# Microcontroller.net
KiCad netlist of a schematic drawn in Altium Designer
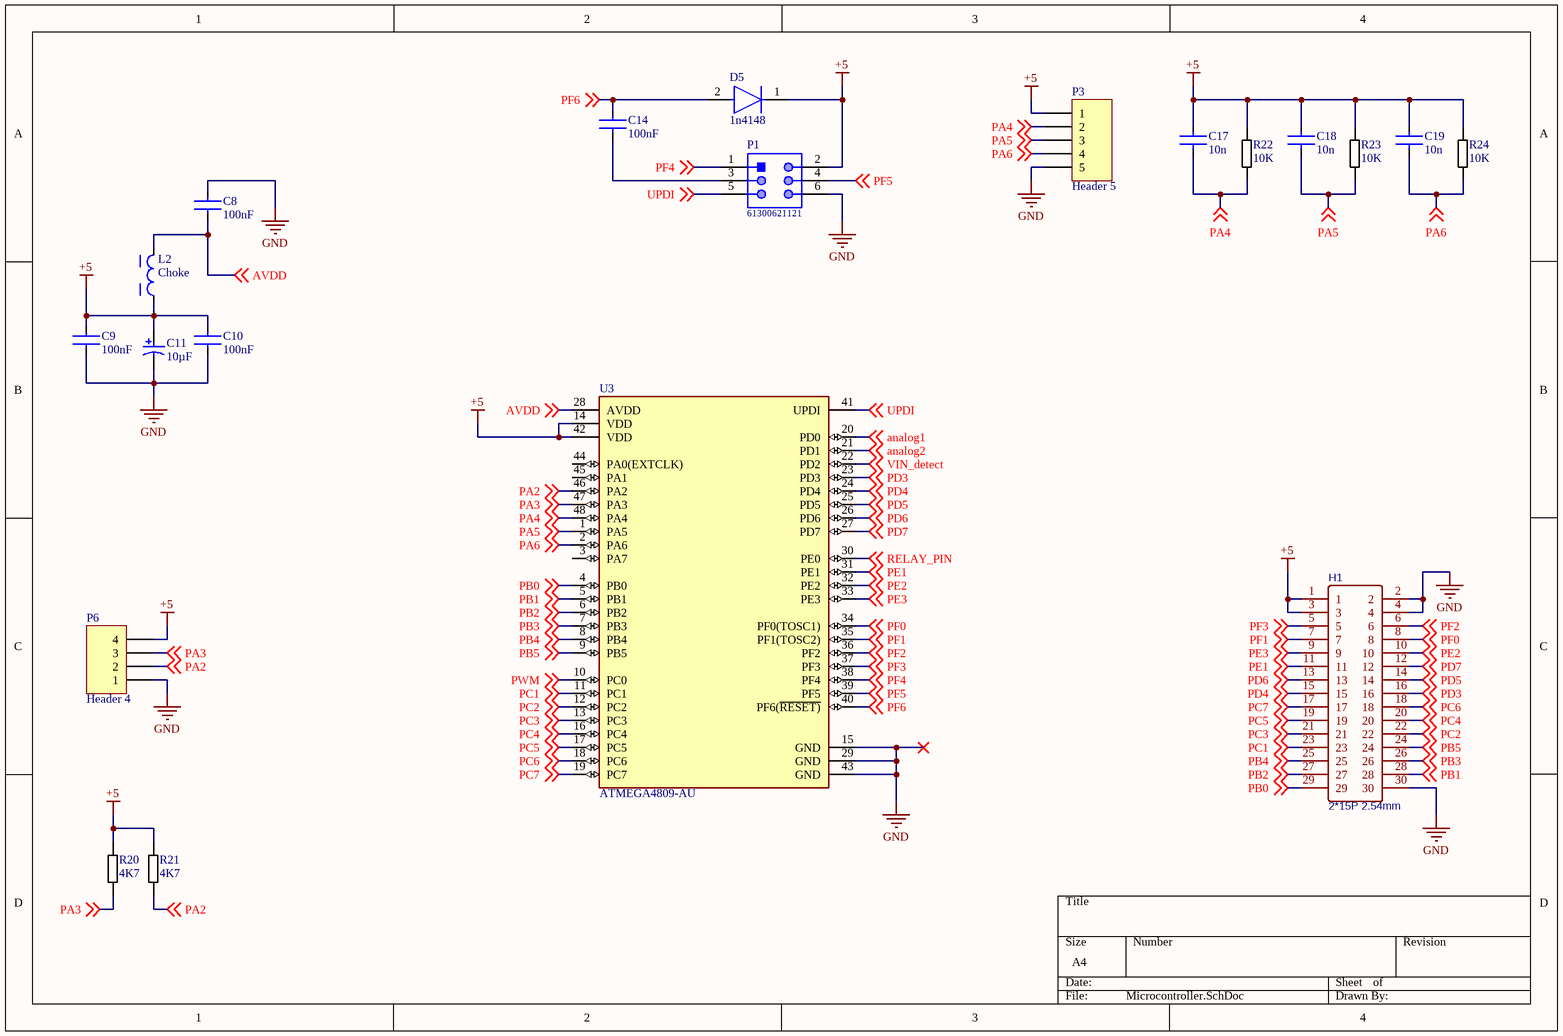
[diagram p0: Microcontroller.SchDoc]

(export (version "E")
  (design (tool "Eeschema 10.0.6"))
  (components
    (comp (ref "C8")
      (value "100nF")
      (footprint "RESC2013X50X30ML20T20")
      (fields (field (name "VOLTAGE") "6.3V") (field (name "TOLERANCE") "20%"))
      (libsource (lib "Soldeerstation") (part "Capacitor"))
    )
    (comp (ref "C9")
      (value "100nF")
      (footprint "RESC2013X50X30ML20T20")
      (fields (field (name "VOLTAGE") "6.3V") (field (name "TOLERANCE") "20%"))
      (libsource (lib "Soldeerstation") (part "Capacitor"))
    )
    (comp (ref "C10")
      (value "100nF")
      (footprint "RESC2013X50X30ML20T20")
      (fields (field (name "VOLTAGE") "6.3V") (field (name "TOLERANCE") "20%"))
      (libsource (lib "Soldeerstation") (part "Capacitor"))
    )
    (comp (ref "C11")
      (value "10µF")
      (footprint "CAP-SMD_BD4.0-L4.3-W4.3-FD-LS5.3")
      (fields (field (name "MANUFACTURER") "Panasonic"))
      (libsource (lib "Soldeerstation") (part "Electrolytic capacitor"))
    )
    (comp (ref "C14")
      (value "100nF")
      (footprint "RESC2013X50X30ML20T20")
      (fields (field (name "VOLTAGE") "6.3V") (field (name "TOLERANCE") "20%"))
      (libsource (lib "Soldeerstation") (part "Capacitor"))
    )
    (comp (ref "C17")
      (value "10n")
      (footprint "RESC2013X50X30ML20T20")
      (fields (field (name "VOLTAGE") "6.3V") (field (name "TOLERANCE") "20%"))
      (libsource (lib "Soldeerstation") (part "Capacitor"))
    )
    (comp (ref "C18")
      (value "10n")
      (footprint "RESC2013X50X30ML20T20")
      (fields (field (name "VOLTAGE") "6.3V") (field (name "TOLERANCE") "20%"))
      (libsource (lib "Soldeerstation") (part "Capacitor"))
    )
    (comp (ref "C19")
      (value "10n")
      (footprint "RESC2013X50X30ML20T20")
      (fields (field (name "VOLTAGE") "6.3V") (field (name "TOLERANCE") "20%"))
      (libsource (lib "Soldeerstation") (part "Capacitor"))
    )
    (comp (ref "D5")
      (value "1n4148")
      (footprint "SOD-123FL")
      (fields
        (field (name "OCTOPART") "https://octopart.com/1n4007-e3%2F54-vishay-39548207")
        (field (name "MANUFACTURER") "Vishay")
        (field (name "MANUFACTURER PART NUMBER") "1N4007-E3/54")
      )
      (libsource (lib "Soldeerstation") (part "Diode"))
    )
    (comp (ref "H1")
      (value "2*15P 2.54mm")
      (footprint "HDR-TH_30P-P2.54-V-M-R2-C15-S2.54")
      (fields
        (field (name "BOM_SUPPLIER PART") "C169817")
        (field (name "BOM_MANUFACTURER PART") "B-2100S30P-B110")
        (field (name "CONTRIBUTOR") "LCSC")
      )
      (libsource (lib "Soldeerstation") (part "2*15P 2.54mm"))
    )
    (comp (ref "L2")
      (value "Choke")
      (footprint "RESC2013X50X30ML20T20")
      (fields (field (name "TOLERANCE") "20%"))
      (libsource (lib "Soldeerstation") (part "Choke"))
    )
    (comp (ref "P1")
      (value "61300621121")
      (footprint "61300621121")
      (description "THT Vertical Pin Header WR-PHD, Pitch 2.54 mm, Dual Row, 6 pins")
      (fields (field (name "MANUFACTURER") "Wurth Elektronik") (field (name "PUBLISHER") "WurthElektronik"))
      (libsource (lib "Altium Content Vault") (part "WE-CN-2P-M-R6"))
    )
    (comp (ref "P3")
      (value "Header 5")
      (footprint "HDR1X5")
      (description "Header, 5-Pin")
      (fields (field (name "PUBLISHER") "Altium Limited"))
      (libsource (lib "Miscellaneous Connectors") (part "Header 5"))
    )
    (comp (ref "P6")
      (value "Header 4")
      (footprint "HDR1X4")
      (description "Header, 4-Pin")
      (fields (field (name "PUBLISHER") "Altium Limited"))
      (libsource (lib "Miscellaneous Connectors") (part "Header 4"))
    )
    (comp (ref "R20")
      (value "4K7")
      (footprint "RESC2013X50X30ML20T20")
      (fields (field (name "MANUFACTURER") "Vishay Dale") (field (name "PART NUMBER") "CRCW08050000Z0EA"))
      (libsource (lib "Soldeerstation") (part "Resistor"))
    )
    (comp (ref "R21")
      (value "4K7")
      (footprint "RESC2013X50X30ML20T20")
      (fields (field (name "MANUFACTURER") "Vishay Dale") (field (name "PART NUMBER") "CRCW08050000Z0EA"))
      (libsource (lib "Soldeerstation") (part "Resistor"))
    )
    (comp (ref "R22")
      (value "10K")
      (footprint "RESC2013X50X30ML20T20")
      (fields (field (name "MANUFACTURER") "Vishay Dale") (field (name "PART NUMBER") "CRCW08050000Z0EA"))
      (libsource (lib "Soldeerstation") (part "Resistor"))
    )
    (comp (ref "R23")
      (value "10K")
      (footprint "RESC2013X50X30ML20T20")
      (fields (field (name "MANUFACTURER") "Vishay Dale") (field (name "PART NUMBER") "CRCW08050000Z0EA"))
      (libsource (lib "Soldeerstation") (part "Resistor"))
    )
    (comp (ref "R24")
      (value "10K")
      (footprint "RESC2013X50X30ML20T20")
      (fields (field (name "MANUFACTURER") "Vishay Dale") (field (name "PART NUMBER") "CRCW08050000Z0EA"))
      (libsource (lib "Soldeerstation") (part "Resistor"))
    )
    (comp (ref "U3")
      (value "ATMEGA4809-AU")
      (footprint "FP-C04-300-PT-IPC_A")
      (description "MCU 8-BIT")
      (libsource (lib "Soldeerstation") (part "MCU"))
    )
  )
  (nets
    (net (code "1") (name "+5") (class "Default")
      (node (ref "C10") (pin "1") (pinfunction "1_1") (pintype "passive"))
      (node (ref "C11") (pin "1") (pinfunction "+_1") (pintype "passive"))
      (node (ref "C17") (pin "1") (pinfunction "1_1") (pintype "passive"))
      (node (ref "C18") (pin "1") (pinfunction "1_1") (pintype "passive"))
      (node (ref "C19") (pin "1") (pinfunction "1_1") (pintype "passive"))
      (node (ref "C9") (pin "1") (pinfunction "1_1") (pintype "passive"))
      (node (ref "D5") (pin "1") (pinfunction "C_1") (pintype "passive"))
      (node (ref "H1") (pin "1") (pinfunction "1_1") (pintype "passive"))
      (node (ref "H1") (pin "3") (pinfunction "3_3") (pintype "passive"))
      (node (ref "L2") (pin "1") (pinfunction "1_1") (pintype "passive"))
      (node (ref "P1") (pin "2") (pinfunction "2_2") (pintype "passive"))
      (node (ref "P3") (pin "1") (pinfunction "1_1") (pintype "passive"))
      (node (ref "P6") (pin "4") (pinfunction "4_4") (pintype "passive"))
      (node (ref "R20") (pin "2") (pinfunction "2_2") (pintype "passive"))
      (node (ref "R21") (pin "2") (pinfunction "2_2") (pintype "passive"))
      (node (ref "R22") (pin "2") (pinfunction "2_2") (pintype "passive"))
      (node (ref "R23") (pin "2") (pinfunction "2_2") (pintype "passive"))
      (node (ref "R24") (pin "2") (pinfunction "2_2") (pintype "passive"))
      (node (ref "U3") (pin "14") (pinfunction "VDD_14") (pintype "power_in"))
      (node (ref "U3") (pin "42") (pinfunction "VDD_42") (pintype "power_in"))
    )
    (net (code "2") (name "AVDD") (class "Default")
      (node (ref "C8") (pin "2") (pinfunction "2_2") (pintype "passive"))
      (node (ref "L2") (pin "2") (pinfunction "2_2") (pintype "passive"))
      (node (ref "U3") (pin "28") (pinfunction "AVDD_28") (pintype "power_in"))
    )
    (net (code "3") (name "GND") (class "Default")
      (node (ref "C10") (pin "2") (pinfunction "2_2") (pintype "passive"))
      (node (ref "C11") (pin "2") (pinfunction "-_2") (pintype "passive"))
      (node (ref "C8") (pin "1") (pinfunction "1_1") (pintype "passive"))
      (node (ref "C9") (pin "2") (pinfunction "2_2") (pintype "passive"))
      (node (ref "H1") (pin "2") (pinfunction "2_2") (pintype "passive"))
      (node (ref "H1") (pin "30") (pinfunction "30_30") (pintype "passive"))
      (node (ref "H1") (pin "4") (pinfunction "4_4") (pintype "passive"))
      (node (ref "P1") (pin "6") (pinfunction "6_6") (pintype "passive"))
      (node (ref "P3") (pin "5") (pinfunction "5_5") (pintype "passive"))
      (node (ref "P6") (pin "1") (pinfunction "1_1") (pintype "passive"))
      (node (ref "U3") (pin "15") (pinfunction "GND_15") (pintype "open_emitter"))
      (node (ref "U3") (pin "29") (pinfunction "GND_29") (pintype "power_in"))
      (node (ref "U3") (pin "43") (pinfunction "GND_43") (pintype "power_in"))
    )
    (net (code "4") (name "Net-(C14-Pad2)") (class "Default")
      (node (ref "C14") (pin "2") (pinfunction "2_2") (pintype "passive"))
      (node (ref "P1") (pin "3") (pinfunction "3_3") (pintype "passive"))
    )
    (net (code "5") (name "PA2") (class "Default")
      (node (ref "P6") (pin "2") (pinfunction "2_2") (pintype "passive"))
      (node (ref "R21") (pin "1") (pinfunction "1_1") (pintype "passive"))
      (node (ref "U3") (pin "46") (pinfunction "PA2_46") (pintype "bidirectional"))
    )
    (net (code "6") (name "PA3") (class "Default")
      (node (ref "P6") (pin "3") (pinfunction "3_3") (pintype "passive"))
      (node (ref "R20") (pin "1") (pinfunction "1_1") (pintype "passive"))
      (node (ref "U3") (pin "47") (pinfunction "PA3_47") (pintype "bidirectional"))
    )
    (net (code "7") (name "PA4") (class "Default")
      (node (ref "C17") (pin "2") (pinfunction "2_2") (pintype "passive"))
      (node (ref "P3") (pin "2") (pinfunction "2_2") (pintype "passive"))
      (node (ref "R22") (pin "1") (pinfunction "1_1") (pintype "passive"))
      (node (ref "U3") (pin "48") (pinfunction "PA4_48") (pintype "bidirectional"))
    )
    (net (code "8") (name "PA5") (class "Default")
      (node (ref "C18") (pin "2") (pinfunction "2_2") (pintype "passive"))
      (node (ref "P3") (pin "3") (pinfunction "3_3") (pintype "passive"))
      (node (ref "R23") (pin "1") (pinfunction "1_1") (pintype "passive"))
      (node (ref "U3") (pin "1") (pinfunction "PA5_1") (pintype "bidirectional"))
    )
    (net (code "9") (name "PA6") (class "Default")
      (node (ref "C19") (pin "2") (pinfunction "2_2") (pintype "passive"))
      (node (ref "P3") (pin "4") (pinfunction "4_4") (pintype "passive"))
      (node (ref "R24") (pin "1") (pinfunction "1_1") (pintype "passive"))
      (node (ref "U3") (pin "2") (pinfunction "PA6_2") (pintype "bidirectional"))
    )
    (net (code "10") (name "PB0") (class "Default")
      (node (ref "H1") (pin "29") (pinfunction "29_29") (pintype "passive"))
      (node (ref "U3") (pin "4") (pinfunction "PB0_4") (pintype "bidirectional"))
    )
    (net (code "11") (name "PB1") (class "Default")
      (node (ref "H1") (pin "28") (pinfunction "28_28") (pintype "passive"))
      (node (ref "U3") (pin "5") (pinfunction "PB1_5") (pintype "bidirectional"))
    )
    (net (code "12") (name "PB2") (class "Default")
      (node (ref "H1") (pin "27") (pinfunction "27_27") (pintype "passive"))
      (node (ref "U3") (pin "6") (pinfunction "PB2_6") (pintype "bidirectional"))
    )
    (net (code "13") (name "PB3") (class "Default")
      (node (ref "H1") (pin "26") (pinfunction "26_26") (pintype "passive"))
      (node (ref "U3") (pin "7") (pinfunction "PB3_7") (pintype "bidirectional"))
    )
    (net (code "14") (name "PB4") (class "Default")
      (node (ref "H1") (pin "25") (pinfunction "25_25") (pintype "passive"))
      (node (ref "U3") (pin "8") (pinfunction "PB4_8") (pintype "bidirectional"))
    )
    (net (code "15") (name "PB5") (class "Default")
      (node (ref "H1") (pin "24") (pinfunction "24_24") (pintype "passive"))
      (node (ref "U3") (pin "9") (pinfunction "PB5_9") (pintype "bidirectional"))
    )
    (net (code "16") (name "PC1") (class "Default")
      (node (ref "H1") (pin "23") (pinfunction "23_23") (pintype "passive"))
      (node (ref "U3") (pin "11") (pinfunction "PC1_11") (pintype "bidirectional"))
    )
    (net (code "17") (name "PC2") (class "Default")
      (node (ref "H1") (pin "22") (pinfunction "22_22") (pintype "passive"))
      (node (ref "U3") (pin "12") (pinfunction "PC2_12") (pintype "bidirectional"))
    )
    (net (code "18") (name "PC3") (class "Default")
      (node (ref "H1") (pin "21") (pinfunction "21_21") (pintype "passive"))
      (node (ref "U3") (pin "13") (pinfunction "PC3_13") (pintype "bidirectional"))
    )
    (net (code "19") (name "PC4") (class "Default")
      (node (ref "H1") (pin "20") (pinfunction "20_20") (pintype "passive"))
      (node (ref "U3") (pin "16") (pinfunction "PC4_16") (pintype "bidirectional"))
    )
    (net (code "20") (name "PC5") (class "Default")
      (node (ref "H1") (pin "19") (pinfunction "19_19") (pintype "passive"))
      (node (ref "U3") (pin "17") (pinfunction "PC5_17") (pintype "bidirectional"))
    )
    (net (code "21") (name "PC6") (class "Default")
      (node (ref "H1") (pin "18") (pinfunction "18_18") (pintype "passive"))
      (node (ref "U3") (pin "18") (pinfunction "PC6_18") (pintype "bidirectional"))
    )
    (net (code "22") (name "PC7") (class "Default")
      (node (ref "H1") (pin "17") (pinfunction "17_17") (pintype "passive"))
      (node (ref "U3") (pin "19") (pinfunction "PC7_19") (pintype "bidirectional"))
    )
    (net (code "23") (name "PD3") (class "Default")
      (node (ref "H1") (pin "16") (pinfunction "16_16") (pintype "passive"))
      (node (ref "U3") (pin "23") (pinfunction "PD3_23") (pintype "bidirectional"))
    )
    (net (code "24") (name "PD4") (class "Default")
      (node (ref "H1") (pin "15") (pinfunction "15_15") (pintype "passive"))
      (node (ref "U3") (pin "24") (pinfunction "PD4_24") (pintype "bidirectional"))
    )
    (net (code "25") (name "PD5") (class "Default")
      (node (ref "H1") (pin "14") (pinfunction "14_14") (pintype "passive"))
      (node (ref "U3") (pin "25") (pinfunction "PD5_25") (pintype "bidirectional"))
    )
    (net (code "26") (name "PD6") (class "Default")
      (node (ref "H1") (pin "13") (pinfunction "13_13") (pintype "passive"))
      (node (ref "U3") (pin "26") (pinfunction "PD6_26") (pintype "bidirectional"))
    )
    (net (code "27") (name "PD7") (class "Default")
      (node (ref "H1") (pin "12") (pinfunction "12_12") (pintype "passive"))
      (node (ref "U3") (pin "27") (pinfunction "PD7_27") (pintype "bidirectional"))
    )
    (net (code "28") (name "PE1") (class "Default")
      (node (ref "H1") (pin "11") (pinfunction "11_11") (pintype "passive"))
      (node (ref "U3") (pin "31") (pinfunction "PE1_31") (pintype "bidirectional"))
    )
    (net (code "29") (name "PE2") (class "Default")
      (node (ref "H1") (pin "10") (pinfunction "10_10") (pintype "passive"))
      (node (ref "U3") (pin "32") (pinfunction "PE2_32") (pintype "bidirectional"))
    )
    (net (code "30") (name "PE3") (class "Default")
      (node (ref "H1") (pin "9") (pinfunction "9_9") (pintype "passive"))
      (node (ref "U3") (pin "33") (pinfunction "PE3_33") (pintype "bidirectional"))
    )
    (net (code "31") (name "PF0") (class "Default")
      (node (ref "H1") (pin "8") (pinfunction "8_8") (pintype "passive"))
      (node (ref "U3") (pin "34") (pinfunction "PF0(TOSC1)_34") (pintype "bidirectional"))
    )
    (net (code "32") (name "PF1") (class "Default")
      (node (ref "H1") (pin "7") (pinfunction "7_7") (pintype "passive"))
      (node (ref "U3") (pin "35") (pinfunction "PF1(TOSC2)_35") (pintype "bidirectional"))
    )
    (net (code "33") (name "PF2") (class "Default")
      (node (ref "H1") (pin "6") (pinfunction "6_6") (pintype "passive"))
      (node (ref "U3") (pin "36") (pinfunction "PF2_36") (pintype "bidirectional"))
    )
    (net (code "34") (name "PF3") (class "Default")
      (node (ref "H1") (pin "5") (pinfunction "5_5") (pintype "passive"))
      (node (ref "U3") (pin "37") (pinfunction "PF3_37") (pintype "bidirectional"))
    )
    (net (code "35") (name "PF4") (class "Default")
      (node (ref "P1") (pin "1") (pinfunction "1_1") (pintype "passive"))
      (node (ref "U3") (pin "38") (pinfunction "PF4_38") (pintype "bidirectional"))
    )
    (net (code "36") (name "PF5") (class "Default")
      (node (ref "P1") (pin "4") (pinfunction "4_4") (pintype "passive"))
      (node (ref "U3") (pin "39") (pinfunction "PF5_39") (pintype "bidirectional"))
    )
    (net (code "37") (name "PF6") (class "Default")
      (node (ref "C14") (pin "1") (pinfunction "1_1") (pintype "passive"))
      (node (ref "D5") (pin "2") (pinfunction "A_2") (pintype "passive"))
      (node (ref "U3") (pin "40") (pinfunction "PF6(~{RESET)}_40") (pintype "bidirectional"))
    )
    (net (code "38") (name "PWM") (class "Default")
      (node (ref "U3") (pin "10") (pinfunction "PC0_10") (pintype "bidirectional"))
    )
    (net (code "39") (name "RELAY_PIN") (class "Default")
      (node (ref "U3") (pin "30") (pinfunction "PE0_30") (pintype "bidirectional"))
    )
    (net (code "40") (name "UPDI") (class "Default")
      (node (ref "P1") (pin "5") (pinfunction "5_5") (pintype "passive"))
      (node (ref "U3") (pin "41") (pinfunction "UPDI_41") (pintype "passive"))
    )
    (net (code "41") (name "VIN_detect") (class "Default")
      (node (ref "U3") (pin "22") (pinfunction "PD2_22") (pintype "bidirectional"))
    )
    (net (code "42") (name "analog1") (class "Default")
      (node (ref "U3") (pin "20") (pinfunction "PD0_20") (pintype "bidirectional"))
    )
    (net (code "43") (name "analog2") (class "Default")
      (node (ref "U3") (pin "21") (pinfunction "PD1_21") (pintype "bidirectional"))
    )
    (net (code "44") (name "unconnected-(U3-PA0(EXTCLK)-Pad44)") (class "Default")
      (node (ref "U3") (pin "44") (pinfunction "PA0(EXTCLK)_44") (pintype "bidirectional"))
    )
    (net (code "45") (name "unconnected-(U3-PA1-Pad45)") (class "Default")
      (node (ref "U3") (pin "45") (pinfunction "PA1_45") (pintype "bidirectional"))
    )
    (net (code "46") (name "unconnected-(U3-PA7-Pad3)") (class "Default")
      (node (ref "U3") (pin "3") (pinfunction "PA7_3") (pintype "bidirectional"))
    )
  )
)
